# room_ind.net
KiCad netlist of a schematic drawn in EAGLE
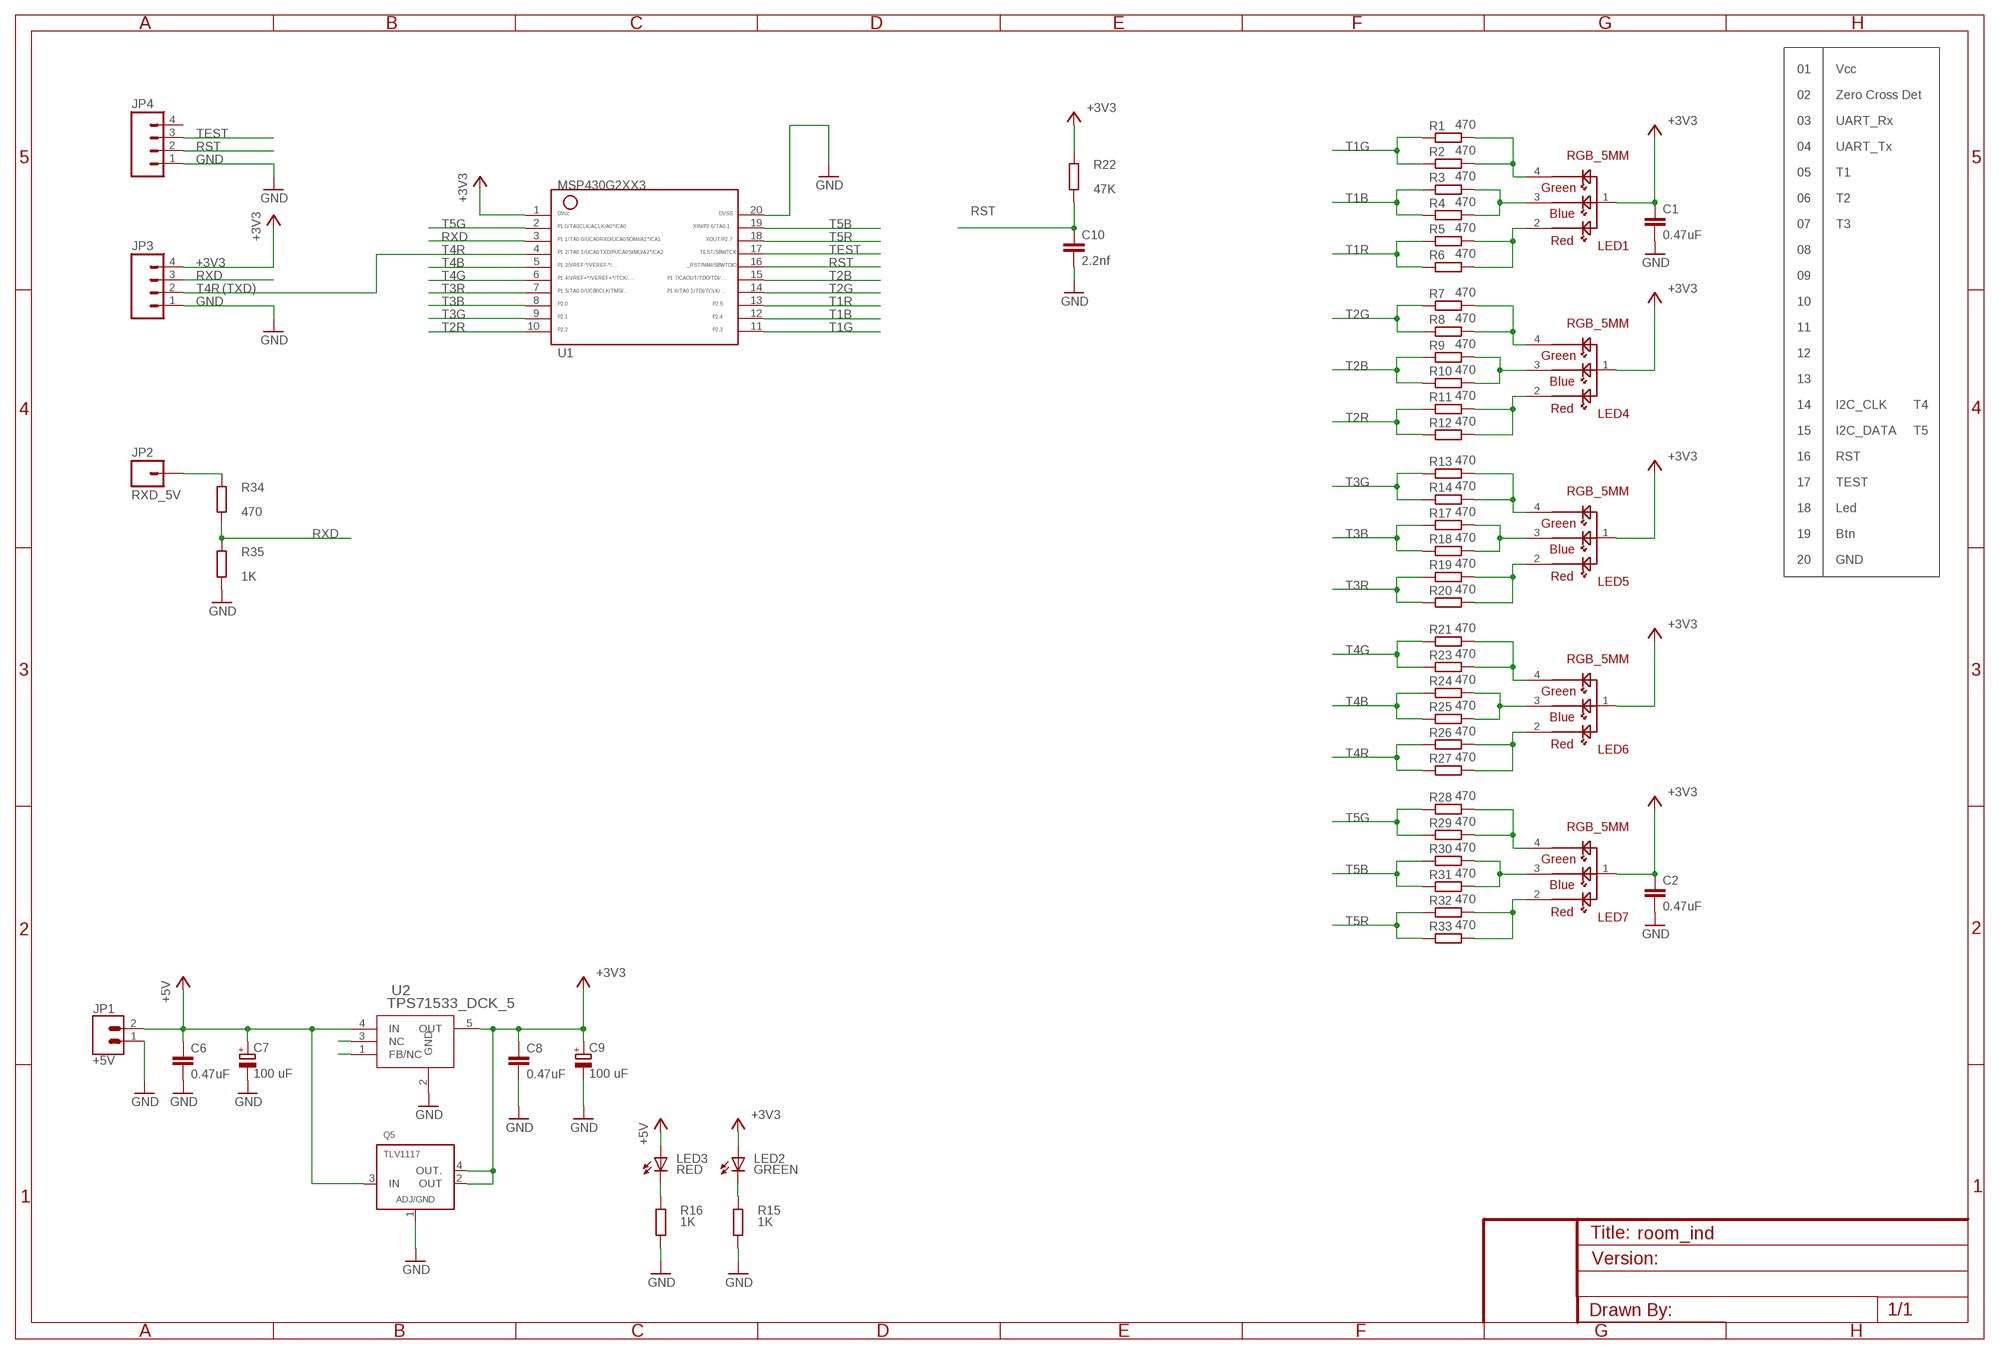
[diagram p0: schematic, sheet 1]

(export (version "E")
  (design (tool "Eeschema 10.0.6"))
  (components
    (comp (ref "C1")
      (value "0.47uF")
      (footprint "eagle-import:C0805")
      (libsource (lib "eagle-import") (part "C-EUC0805"))
    )
    (comp (ref "C2")
      (value "0.47uF")
      (footprint "eagle-import:C0805")
      (libsource (lib "eagle-import") (part "C-EUC0805"))
    )
    (comp (ref "C6")
      (value "0.47uF")
      (footprint "eagle-import:C0805")
      (libsource (lib "eagle-import") (part "C-EUC0805"))
    )
    (comp (ref "C7")
      (value "100 uF")
      (footprint "eagle-import:E2,5-7")
      (libsource (lib "eagle-import") (part "CPOL-EUE2.5-7"))
    )
    (comp (ref "C8")
      (value "0.47uF")
      (footprint "eagle-import:C0805")
      (libsource (lib "eagle-import") (part "C-EUC0805"))
    )
    (comp (ref "C9")
      (value "100 uF")
      (footprint "eagle-import:E2,5-7")
      (libsource (lib "eagle-import") (part "CPOL-EUE2.5-7"))
    )
    (comp (ref "C10")
      (value "2.2nf")
      (footprint "eagle-import:C0805")
      (libsource (lib "eagle-import") (part "C-EUC0805"))
    )
    (comp (ref "JP1")
      (value "+5V")
      (footprint "eagle-import:BLUE_TERM")
      (libsource (lib "eagle-import") (part "BLUE_TERM"))
    )
    (comp (ref "JP2")
      (value "RXD_5V")
      (footprint "eagle-import:1X01")
      (libsource (lib "eagle-import") (part "M01PTH"))
    )
    (comp (ref "JP3")
      (value "M04PTH")
      (footprint "eagle-import:1X04")
      (libsource (lib "eagle-import") (part "M04PTH"))
    )
    (comp (ref "JP4")
      (value "M04PTH")
      (footprint "eagle-import:1X04")
      (libsource (lib "eagle-import") (part "M04PTH"))
    )
    (comp (ref "LED1")
      (value "RGB_5MM")
      (footprint "eagle-import:RGB_5MM")
      (libsource (lib "eagle-import") (part "RGB_5MM"))
    )
    (comp (ref "LED2")
      (value "GREEN")
      (footprint "eagle-import:CHIP-LED0805")
      (libsource (lib "eagle-import") (part "LEDCHIP-LED0805"))
    )
    (comp (ref "LED3")
      (value "RED")
      (footprint "eagle-import:CHIP-LED0805")
      (libsource (lib "eagle-import") (part "LEDCHIP-LED0805"))
    )
    (comp (ref "LED4")
      (value "RGB_5MM")
      (footprint "eagle-import:RGB_5MM")
      (libsource (lib "eagle-import") (part "RGB_5MM"))
    )
    (comp (ref "LED5")
      (value "RGB_5MM")
      (footprint "eagle-import:RGB_5MM")
      (libsource (lib "eagle-import") (part "RGB_5MM"))
    )
    (comp (ref "LED6")
      (value "RGB_5MM")
      (footprint "eagle-import:RGB_5MM")
      (libsource (lib "eagle-import") (part "RGB_5MM"))
    )
    (comp (ref "LED7")
      (value "RGB_5MM")
      (footprint "eagle-import:RGB_5MM")
      (libsource (lib "eagle-import") (part "RGB_5MM"))
    )
    (comp (ref "Q5")
      (value "TLV1117")
      (footprint "eagle-import:SOT223-4")
      (libsource (lib "eagle-import") (part "TLV1117"))
    )
    (comp (ref "R1")
      (value "470")
      (footprint "eagle-import:R0805")
      (libsource (lib "eagle-import") (part "R-EU_R0805"))
    )
    (comp (ref "R2")
      (value "470")
      (footprint "eagle-import:0207_7")
      (libsource (lib "eagle-import") (part "R-EU_0207/7"))
    )
    (comp (ref "R3")
      (value "470")
      (footprint "eagle-import:R0805")
      (libsource (lib "eagle-import") (part "R-EU_R0805"))
    )
    (comp (ref "R4")
      (value "470")
      (footprint "eagle-import:0207_7")
      (libsource (lib "eagle-import") (part "R-EU_0207/7"))
    )
    (comp (ref "R5")
      (value "470")
      (footprint "eagle-import:R0805")
      (libsource (lib "eagle-import") (part "R-EU_R0805"))
    )
    (comp (ref "R6")
      (value "470")
      (footprint "eagle-import:0207_7")
      (libsource (lib "eagle-import") (part "R-EU_0207/7"))
    )
    (comp (ref "R7")
      (value "470")
      (footprint "eagle-import:R0805")
      (libsource (lib "eagle-import") (part "R-EU_R0805"))
    )
    (comp (ref "R8")
      (value "470")
      (footprint "eagle-import:0207_7")
      (libsource (lib "eagle-import") (part "R-EU_0207/7"))
    )
    (comp (ref "R9")
      (value "470")
      (footprint "eagle-import:R0805")
      (libsource (lib "eagle-import") (part "R-EU_R0805"))
    )
    (comp (ref "R10")
      (value "470")
      (footprint "eagle-import:0207_7")
      (libsource (lib "eagle-import") (part "R-EU_0207/7"))
    )
    (comp (ref "R11")
      (value "470")
      (footprint "eagle-import:R0805")
      (libsource (lib "eagle-import") (part "R-EU_R0805"))
    )
    (comp (ref "R12")
      (value "470")
      (footprint "eagle-import:0207_7")
      (libsource (lib "eagle-import") (part "R-EU_0207/7"))
    )
    (comp (ref "R13")
      (value "470")
      (footprint "eagle-import:R0805")
      (libsource (lib "eagle-import") (part "R-EU_R0805"))
    )
    (comp (ref "R14")
      (value "470")
      (footprint "eagle-import:0207_7")
      (libsource (lib "eagle-import") (part "R-EU_0207/7"))
    )
    (comp (ref "R15")
      (value "1K")
      (footprint "eagle-import:R0805")
      (libsource (lib "eagle-import") (part "R-EU_R0805"))
    )
    (comp (ref "R16")
      (value "1K")
      (footprint "eagle-import:R0805")
      (libsource (lib "eagle-import") (part "R-EU_R0805"))
    )
    (comp (ref "R17")
      (value "470")
      (footprint "eagle-import:R0805")
      (libsource (lib "eagle-import") (part "R-EU_R0805"))
    )
    (comp (ref "R18")
      (value "470")
      (footprint "eagle-import:0207_7")
      (libsource (lib "eagle-import") (part "R-EU_0207/7"))
    )
    (comp (ref "R19")
      (value "470")
      (footprint "eagle-import:R0805")
      (libsource (lib "eagle-import") (part "R-EU_R0805"))
    )
    (comp (ref "R20")
      (value "470")
      (footprint "eagle-import:0207_7")
      (libsource (lib "eagle-import") (part "R-EU_0207/7"))
    )
    (comp (ref "R21")
      (value "470")
      (footprint "eagle-import:R0805")
      (libsource (lib "eagle-import") (part "R-EU_R0805"))
    )
    (comp (ref "R22")
      (value "47K")
      (footprint "eagle-import:R0805")
      (libsource (lib "eagle-import") (part "R-EU_R0805"))
    )
    (comp (ref "R23")
      (value "470")
      (footprint "eagle-import:0207_7")
      (libsource (lib "eagle-import") (part "R-EU_0207/7"))
    )
    (comp (ref "R24")
      (value "470")
      (footprint "eagle-import:R0805")
      (libsource (lib "eagle-import") (part "R-EU_R0805"))
    )
    (comp (ref "R25")
      (value "470")
      (footprint "eagle-import:0207_7")
      (libsource (lib "eagle-import") (part "R-EU_0207/7"))
    )
    (comp (ref "R26")
      (value "470")
      (footprint "eagle-import:R0805")
      (libsource (lib "eagle-import") (part "R-EU_R0805"))
    )
    (comp (ref "R27")
      (value "470")
      (footprint "eagle-import:0207_7")
      (libsource (lib "eagle-import") (part "R-EU_0207/7"))
    )
    (comp (ref "R28")
      (value "470")
      (footprint "eagle-import:R0805")
      (libsource (lib "eagle-import") (part "R-EU_R0805"))
    )
    (comp (ref "R29")
      (value "470")
      (footprint "eagle-import:0207_7")
      (libsource (lib "eagle-import") (part "R-EU_0207/7"))
    )
    (comp (ref "R30")
      (value "470")
      (footprint "eagle-import:R0805")
      (libsource (lib "eagle-import") (part "R-EU_R0805"))
    )
    (comp (ref "R31")
      (value "470")
      (footprint "eagle-import:0207_7")
      (libsource (lib "eagle-import") (part "R-EU_0207/7"))
    )
    (comp (ref "R32")
      (value "470")
      (footprint "eagle-import:R0805")
      (libsource (lib "eagle-import") (part "R-EU_R0805"))
    )
    (comp (ref "R33")
      (value "470")
      (footprint "eagle-import:0207_7")
      (libsource (lib "eagle-import") (part "R-EU_0207/7"))
    )
    (comp (ref "R34")
      (value "470")
      (footprint "eagle-import:R0805")
      (libsource (lib "eagle-import") (part "R-EU_R0805"))
    )
    (comp (ref "R35")
      (value "1K")
      (footprint "eagle-import:R0805")
      (libsource (lib "eagle-import") (part "R-EU_R0805"))
    )
    (comp (ref "U1")
      (value "G2XX3---PW20")
      (footprint "eagle-import:PW20")
      (libsource (lib "eagle-import") (part "G2XX3---PW20"))
    )
    (comp (ref "U2")
      (value "TPS71533_DCK_5")
      (footprint "eagle-import:DCK5")
      (fields
        (field (name "GENERIC_PART_NUMBER") "TPS71533")
        (field (name "MANUFACTURER") "Texas Instruments")
        (field (name "MANUFACTURER_PART_NUMBER") "tps71533_dck_5")
      )
      (libsource (lib "eagle-import") (part "TPS71533_DCK_5"))
    )
  )
  (nets
    (net (code "1") (name "+3V3") (class "Default")
      (node (ref "C1") (pin "1") (pinfunction "1_1") (pintype "passive"))
      (node (ref "C2") (pin "1") (pinfunction "1_1") (pintype "passive"))
      (node (ref "C8") (pin "1") (pinfunction "1_1") (pintype "passive"))
      (node (ref "C9") (pin "+") (pinfunction "+_+") (pintype "passive"))
      (node (ref "JP3") (pin "4") (pinfunction "4_4") (pintype "passive"))
      (node (ref "LED1") (pin "1") (pinfunction "1_1") (pintype "bidirectional"))
      (node (ref "LED2") (pin "A") (pinfunction "A_A") (pintype "passive"))
      (node (ref "LED4") (pin "1") (pinfunction "1_1") (pintype "bidirectional"))
      (node (ref "LED5") (pin "1") (pinfunction "1_1") (pintype "bidirectional"))
      (node (ref "LED6") (pin "1") (pinfunction "1_1") (pintype "bidirectional"))
      (node (ref "LED7") (pin "1") (pinfunction "1_1") (pintype "bidirectional"))
      (node (ref "Q5") (pin "2") (pinfunction "OUT_2") (pintype "power_in"))
      (node (ref "Q5") (pin "4") (pinfunction "OUT._4") (pintype "power_in"))
      (node (ref "R22") (pin "2") (pinfunction "2_2") (pintype "passive"))
      (node (ref "U1") (pin "1") (pinfunction "1_1") (pintype "bidirectional"))
      (node (ref "U2") (pin "5") (pinfunction "OUT_5") (pintype "power_in"))
    )
    (net (code "2") (name "+5V") (class "Default")
      (node (ref "C6") (pin "1") (pinfunction "1_1") (pintype "passive"))
      (node (ref "C7") (pin "+") (pinfunction "+_+") (pintype "passive"))
      (node (ref "JP1") (pin "2") (pinfunction "2_2") (pintype "passive"))
      (node (ref "LED3") (pin "A") (pinfunction "A_A") (pintype "passive"))
      (node (ref "Q5") (pin "3") (pinfunction "IN_3") (pintype "power_in"))
      (node (ref "U2") (pin "4") (pinfunction "IN_4") (pintype "power_in"))
    )
    (net (code "3") (name "/RST") (class "Default")
      (node (ref "C10") (pin "1") (pinfunction "1_1") (pintype "passive"))
      (node (ref "JP4") (pin "2") (pinfunction "2_2") (pintype "passive"))
      (node (ref "R22") (pin "1") (pinfunction "1_1") (pintype "passive"))
      (node (ref "U1") (pin "16") (pinfunction "16_16") (pintype "bidirectional"))
    )
    (net (code "4") (name "/RXD") (class "Default")
      (node (ref "JP3") (pin "3") (pinfunction "3_3") (pintype "passive"))
      (node (ref "R34") (pin "1") (pinfunction "1_1") (pintype "passive"))
      (node (ref "R35") (pin "2") (pinfunction "2_2") (pintype "passive"))
      (node (ref "U1") (pin "3") (pinfunction "3_3") (pintype "bidirectional"))
    )
    (net (code "5") (name "/T1B") (class "Default")
      (node (ref "R3") (pin "1") (pinfunction "1_1") (pintype "passive"))
      (node (ref "R4") (pin "1") (pinfunction "1_1") (pintype "passive"))
      (node (ref "U1") (pin "12") (pinfunction "12_12") (pintype "bidirectional"))
    )
    (net (code "6") (name "/T1G") (class "Default")
      (node (ref "R1") (pin "1") (pinfunction "1_1") (pintype "passive"))
      (node (ref "R2") (pin "1") (pinfunction "1_1") (pintype "passive"))
      (node (ref "U1") (pin "11") (pinfunction "11_11") (pintype "bidirectional"))
    )
    (net (code "7") (name "/T1R") (class "Default")
      (node (ref "R5") (pin "1") (pinfunction "1_1") (pintype "passive"))
      (node (ref "R6") (pin "1") (pinfunction "1_1") (pintype "passive"))
      (node (ref "U1") (pin "13") (pinfunction "13_13") (pintype "bidirectional"))
    )
    (net (code "8") (name "/T2B") (class "Default")
      (node (ref "R10") (pin "1") (pinfunction "1_1") (pintype "passive"))
      (node (ref "R9") (pin "1") (pinfunction "1_1") (pintype "passive"))
      (node (ref "U1") (pin "15") (pinfunction "15_15") (pintype "bidirectional"))
    )
    (net (code "9") (name "/T2G") (class "Default")
      (node (ref "R7") (pin "1") (pinfunction "1_1") (pintype "passive"))
      (node (ref "R8") (pin "1") (pinfunction "1_1") (pintype "passive"))
      (node (ref "U1") (pin "14") (pinfunction "14_14") (pintype "bidirectional"))
    )
    (net (code "10") (name "/T2R") (class "Default")
      (node (ref "R11") (pin "1") (pinfunction "1_1") (pintype "passive"))
      (node (ref "R12") (pin "1") (pinfunction "1_1") (pintype "passive"))
      (node (ref "U1") (pin "10") (pinfunction "10_10") (pintype "bidirectional"))
    )
    (net (code "11") (name "/T3B") (class "Default")
      (node (ref "R17") (pin "1") (pinfunction "1_1") (pintype "passive"))
      (node (ref "R18") (pin "1") (pinfunction "1_1") (pintype "passive"))
      (node (ref "U1") (pin "8") (pinfunction "8_8") (pintype "bidirectional"))
    )
    (net (code "12") (name "/T3G") (class "Default")
      (node (ref "R13") (pin "1") (pinfunction "1_1") (pintype "passive"))
      (node (ref "R14") (pin "1") (pinfunction "1_1") (pintype "passive"))
      (node (ref "U1") (pin "9") (pinfunction "9_9") (pintype "bidirectional"))
    )
    (net (code "13") (name "/T3R") (class "Default")
      (node (ref "R19") (pin "1") (pinfunction "1_1") (pintype "passive"))
      (node (ref "R20") (pin "1") (pinfunction "1_1") (pintype "passive"))
      (node (ref "U1") (pin "7") (pinfunction "7_7") (pintype "bidirectional"))
    )
    (net (code "14") (name "/T4B") (class "Default")
      (node (ref "R24") (pin "1") (pinfunction "1_1") (pintype "passive"))
      (node (ref "R25") (pin "1") (pinfunction "1_1") (pintype "passive"))
      (node (ref "U1") (pin "5") (pinfunction "5_5") (pintype "bidirectional"))
    )
    (net (code "15") (name "/T4G") (class "Default")
      (node (ref "R21") (pin "1") (pinfunction "1_1") (pintype "passive"))
      (node (ref "R23") (pin "1") (pinfunction "1_1") (pintype "passive"))
      (node (ref "U1") (pin "6") (pinfunction "6_6") (pintype "bidirectional"))
    )
    (net (code "16") (name "/T4R") (class "Default")
      (node (ref "JP3") (pin "2") (pinfunction "2_2") (pintype "passive"))
      (node (ref "R26") (pin "1") (pinfunction "1_1") (pintype "passive"))
      (node (ref "R27") (pin "1") (pinfunction "1_1") (pintype "passive"))
      (node (ref "U1") (pin "4") (pinfunction "4_4") (pintype "bidirectional"))
    )
    (net (code "17") (name "/T5B") (class "Default")
      (node (ref "R30") (pin "1") (pinfunction "1_1") (pintype "passive"))
      (node (ref "R31") (pin "1") (pinfunction "1_1") (pintype "passive"))
      (node (ref "U1") (pin "19") (pinfunction "19_19") (pintype "bidirectional"))
    )
    (net (code "18") (name "/T5G") (class "Default")
      (node (ref "R28") (pin "1") (pinfunction "1_1") (pintype "passive"))
      (node (ref "R29") (pin "1") (pinfunction "1_1") (pintype "passive"))
      (node (ref "U1") (pin "2") (pinfunction "2_2") (pintype "bidirectional"))
    )
    (net (code "19") (name "/T5R") (class "Default")
      (node (ref "R32") (pin "1") (pinfunction "1_1") (pintype "passive"))
      (node (ref "R33") (pin "1") (pinfunction "1_1") (pintype "passive"))
      (node (ref "U1") (pin "18") (pinfunction "18_18") (pintype "bidirectional"))
    )
    (net (code "20") (name "/TEST") (class "Default")
      (node (ref "JP4") (pin "3") (pinfunction "3_3") (pintype "passive"))
      (node (ref "U1") (pin "17") (pinfunction "17_17") (pintype "bidirectional"))
    )
    (net (code "21") (name "GND") (class "Default")
      (node (ref "C1") (pin "2") (pinfunction "2_2") (pintype "passive"))
      (node (ref "C10") (pin "2") (pinfunction "2_2") (pintype "passive"))
      (node (ref "C2") (pin "2") (pinfunction "2_2") (pintype "passive"))
      (node (ref "C6") (pin "2") (pinfunction "2_2") (pintype "passive"))
      (node (ref "C7") (pin "-") (pinfunction "-_-") (pintype "passive"))
      (node (ref "C8") (pin "2") (pinfunction "2_2") (pintype "passive"))
      (node (ref "C9") (pin "-") (pinfunction "-_-") (pintype "passive"))
      (node (ref "JP1") (pin "1") (pinfunction "1_1") (pintype "passive"))
      (node (ref "JP3") (pin "1") (pinfunction "1_1") (pintype "passive"))
      (node (ref "JP4") (pin "1") (pinfunction "1_1") (pintype "passive"))
      (node (ref "Q5") (pin "1") (pinfunction "ADJ/GND_1") (pintype "bidirectional"))
      (node (ref "R15") (pin "1") (pinfunction "1_1") (pintype "passive"))
      (node (ref "R16") (pin "1") (pinfunction "1_1") (pintype "passive"))
      (node (ref "R35") (pin "1") (pinfunction "1_1") (pintype "passive"))
      (node (ref "U1") (pin "20") (pinfunction "20_20") (pintype "bidirectional"))
      (node (ref "U2") (pin "2") (pinfunction "GND_2") (pintype "power_in"))
    )
    (net (code "22") (name "Net-(JP2-Pad1)") (class "Default")
      (node (ref "JP2") (pin "1") (pinfunction "1_1") (pintype "passive"))
      (node (ref "R34") (pin "2") (pinfunction "2_2") (pintype "passive"))
    )
    (net (code "23") (name "Net-(LED1-Pad2)") (class "Default")
      (node (ref "LED1") (pin "2") (pinfunction "2_2") (pintype "bidirectional"))
      (node (ref "R5") (pin "2") (pinfunction "2_2") (pintype "passive"))
      (node (ref "R6") (pin "2") (pinfunction "2_2") (pintype "passive"))
    )
    (net (code "24") (name "Net-(LED1-Pad3)") (class "Default")
      (node (ref "LED1") (pin "3") (pinfunction "3_3") (pintype "bidirectional"))
      (node (ref "R3") (pin "2") (pinfunction "2_2") (pintype "passive"))
      (node (ref "R4") (pin "2") (pinfunction "2_2") (pintype "passive"))
    )
    (net (code "25") (name "Net-(LED1-Pad4)") (class "Default")
      (node (ref "LED1") (pin "4") (pinfunction "4_4") (pintype "bidirectional"))
      (node (ref "R1") (pin "2") (pinfunction "2_2") (pintype "passive"))
      (node (ref "R2") (pin "2") (pinfunction "2_2") (pintype "passive"))
    )
    (net (code "26") (name "Net-(LED2-PadC)") (class "Default")
      (node (ref "LED2") (pin "C") (pinfunction "C_C") (pintype "passive"))
      (node (ref "R15") (pin "2") (pinfunction "2_2") (pintype "passive"))
    )
    (net (code "27") (name "Net-(LED3-PadC)") (class "Default")
      (node (ref "LED3") (pin "C") (pinfunction "C_C") (pintype "passive"))
      (node (ref "R16") (pin "2") (pinfunction "2_2") (pintype "passive"))
    )
    (net (code "28") (name "Net-(LED4-Pad2)") (class "Default")
      (node (ref "LED4") (pin "2") (pinfunction "2_2") (pintype "bidirectional"))
      (node (ref "R11") (pin "2") (pinfunction "2_2") (pintype "passive"))
      (node (ref "R12") (pin "2") (pinfunction "2_2") (pintype "passive"))
    )
    (net (code "29") (name "Net-(LED4-Pad3)") (class "Default")
      (node (ref "LED4") (pin "3") (pinfunction "3_3") (pintype "bidirectional"))
      (node (ref "R10") (pin "2") (pinfunction "2_2") (pintype "passive"))
      (node (ref "R9") (pin "2") (pinfunction "2_2") (pintype "passive"))
    )
    (net (code "30") (name "Net-(LED4-Pad4)") (class "Default")
      (node (ref "LED4") (pin "4") (pinfunction "4_4") (pintype "bidirectional"))
      (node (ref "R7") (pin "2") (pinfunction "2_2") (pintype "passive"))
      (node (ref "R8") (pin "2") (pinfunction "2_2") (pintype "passive"))
    )
    (net (code "31") (name "Net-(LED5-Pad2)") (class "Default")
      (node (ref "LED5") (pin "2") (pinfunction "2_2") (pintype "bidirectional"))
      (node (ref "R19") (pin "2") (pinfunction "2_2") (pintype "passive"))
      (node (ref "R20") (pin "2") (pinfunction "2_2") (pintype "passive"))
    )
    (net (code "32") (name "Net-(LED5-Pad3)") (class "Default")
      (node (ref "LED5") (pin "3") (pinfunction "3_3") (pintype "bidirectional"))
      (node (ref "R17") (pin "2") (pinfunction "2_2") (pintype "passive"))
      (node (ref "R18") (pin "2") (pinfunction "2_2") (pintype "passive"))
    )
    (net (code "33") (name "Net-(LED5-Pad4)") (class "Default")
      (node (ref "LED5") (pin "4") (pinfunction "4_4") (pintype "bidirectional"))
      (node (ref "R13") (pin "2") (pinfunction "2_2") (pintype "passive"))
      (node (ref "R14") (pin "2") (pinfunction "2_2") (pintype "passive"))
    )
    (net (code "34") (name "Net-(LED6-Pad2)") (class "Default")
      (node (ref "LED6") (pin "2") (pinfunction "2_2") (pintype "bidirectional"))
      (node (ref "R26") (pin "2") (pinfunction "2_2") (pintype "passive"))
      (node (ref "R27") (pin "2") (pinfunction "2_2") (pintype "passive"))
    )
    (net (code "35") (name "Net-(LED6-Pad3)") (class "Default")
      (node (ref "LED6") (pin "3") (pinfunction "3_3") (pintype "bidirectional"))
      (node (ref "R24") (pin "2") (pinfunction "2_2") (pintype "passive"))
      (node (ref "R25") (pin "2") (pinfunction "2_2") (pintype "passive"))
    )
    (net (code "36") (name "Net-(LED6-Pad4)") (class "Default")
      (node (ref "LED6") (pin "4") (pinfunction "4_4") (pintype "bidirectional"))
      (node (ref "R21") (pin "2") (pinfunction "2_2") (pintype "passive"))
      (node (ref "R23") (pin "2") (pinfunction "2_2") (pintype "passive"))
    )
    (net (code "37") (name "Net-(LED7-Pad2)") (class "Default")
      (node (ref "LED7") (pin "2") (pinfunction "2_2") (pintype "bidirectional"))
      (node (ref "R32") (pin "2") (pinfunction "2_2") (pintype "passive"))
      (node (ref "R33") (pin "2") (pinfunction "2_2") (pintype "passive"))
    )
    (net (code "38") (name "Net-(LED7-Pad3)") (class "Default")
      (node (ref "LED7") (pin "3") (pinfunction "3_3") (pintype "bidirectional"))
      (node (ref "R30") (pin "2") (pinfunction "2_2") (pintype "passive"))
      (node (ref "R31") (pin "2") (pinfunction "2_2") (pintype "passive"))
    )
    (net (code "39") (name "Net-(LED7-Pad4)") (class "Default")
      (node (ref "LED7") (pin "4") (pinfunction "4_4") (pintype "bidirectional"))
      (node (ref "R28") (pin "2") (pinfunction "2_2") (pintype "passive"))
      (node (ref "R29") (pin "2") (pinfunction "2_2") (pintype "passive"))
    )
    (net (code "40") (name "unconnected-(JP4-Pad4)") (class "Default")
      (node (ref "JP4") (pin "4") (pinfunction "4_4") (pintype "passive"))
    )
    (net (code "41") (name "unconnected-(U2-FB{slash}NC-Pad1)") (class "Default")
      (node (ref "U2") (pin "1") (pinfunction "FB/NC_1") (pintype "input"))
    )
    (net (code "42") (name "unconnected-(U2-NC-Pad3)") (class "Default")
      (node (ref "U2") (pin "3") (pinfunction "NC_3") (pintype "no_connect"))
    )
  )
)
